# WIFI_BT.net
KiCad netlist of a schematic drawn in Altium Designer
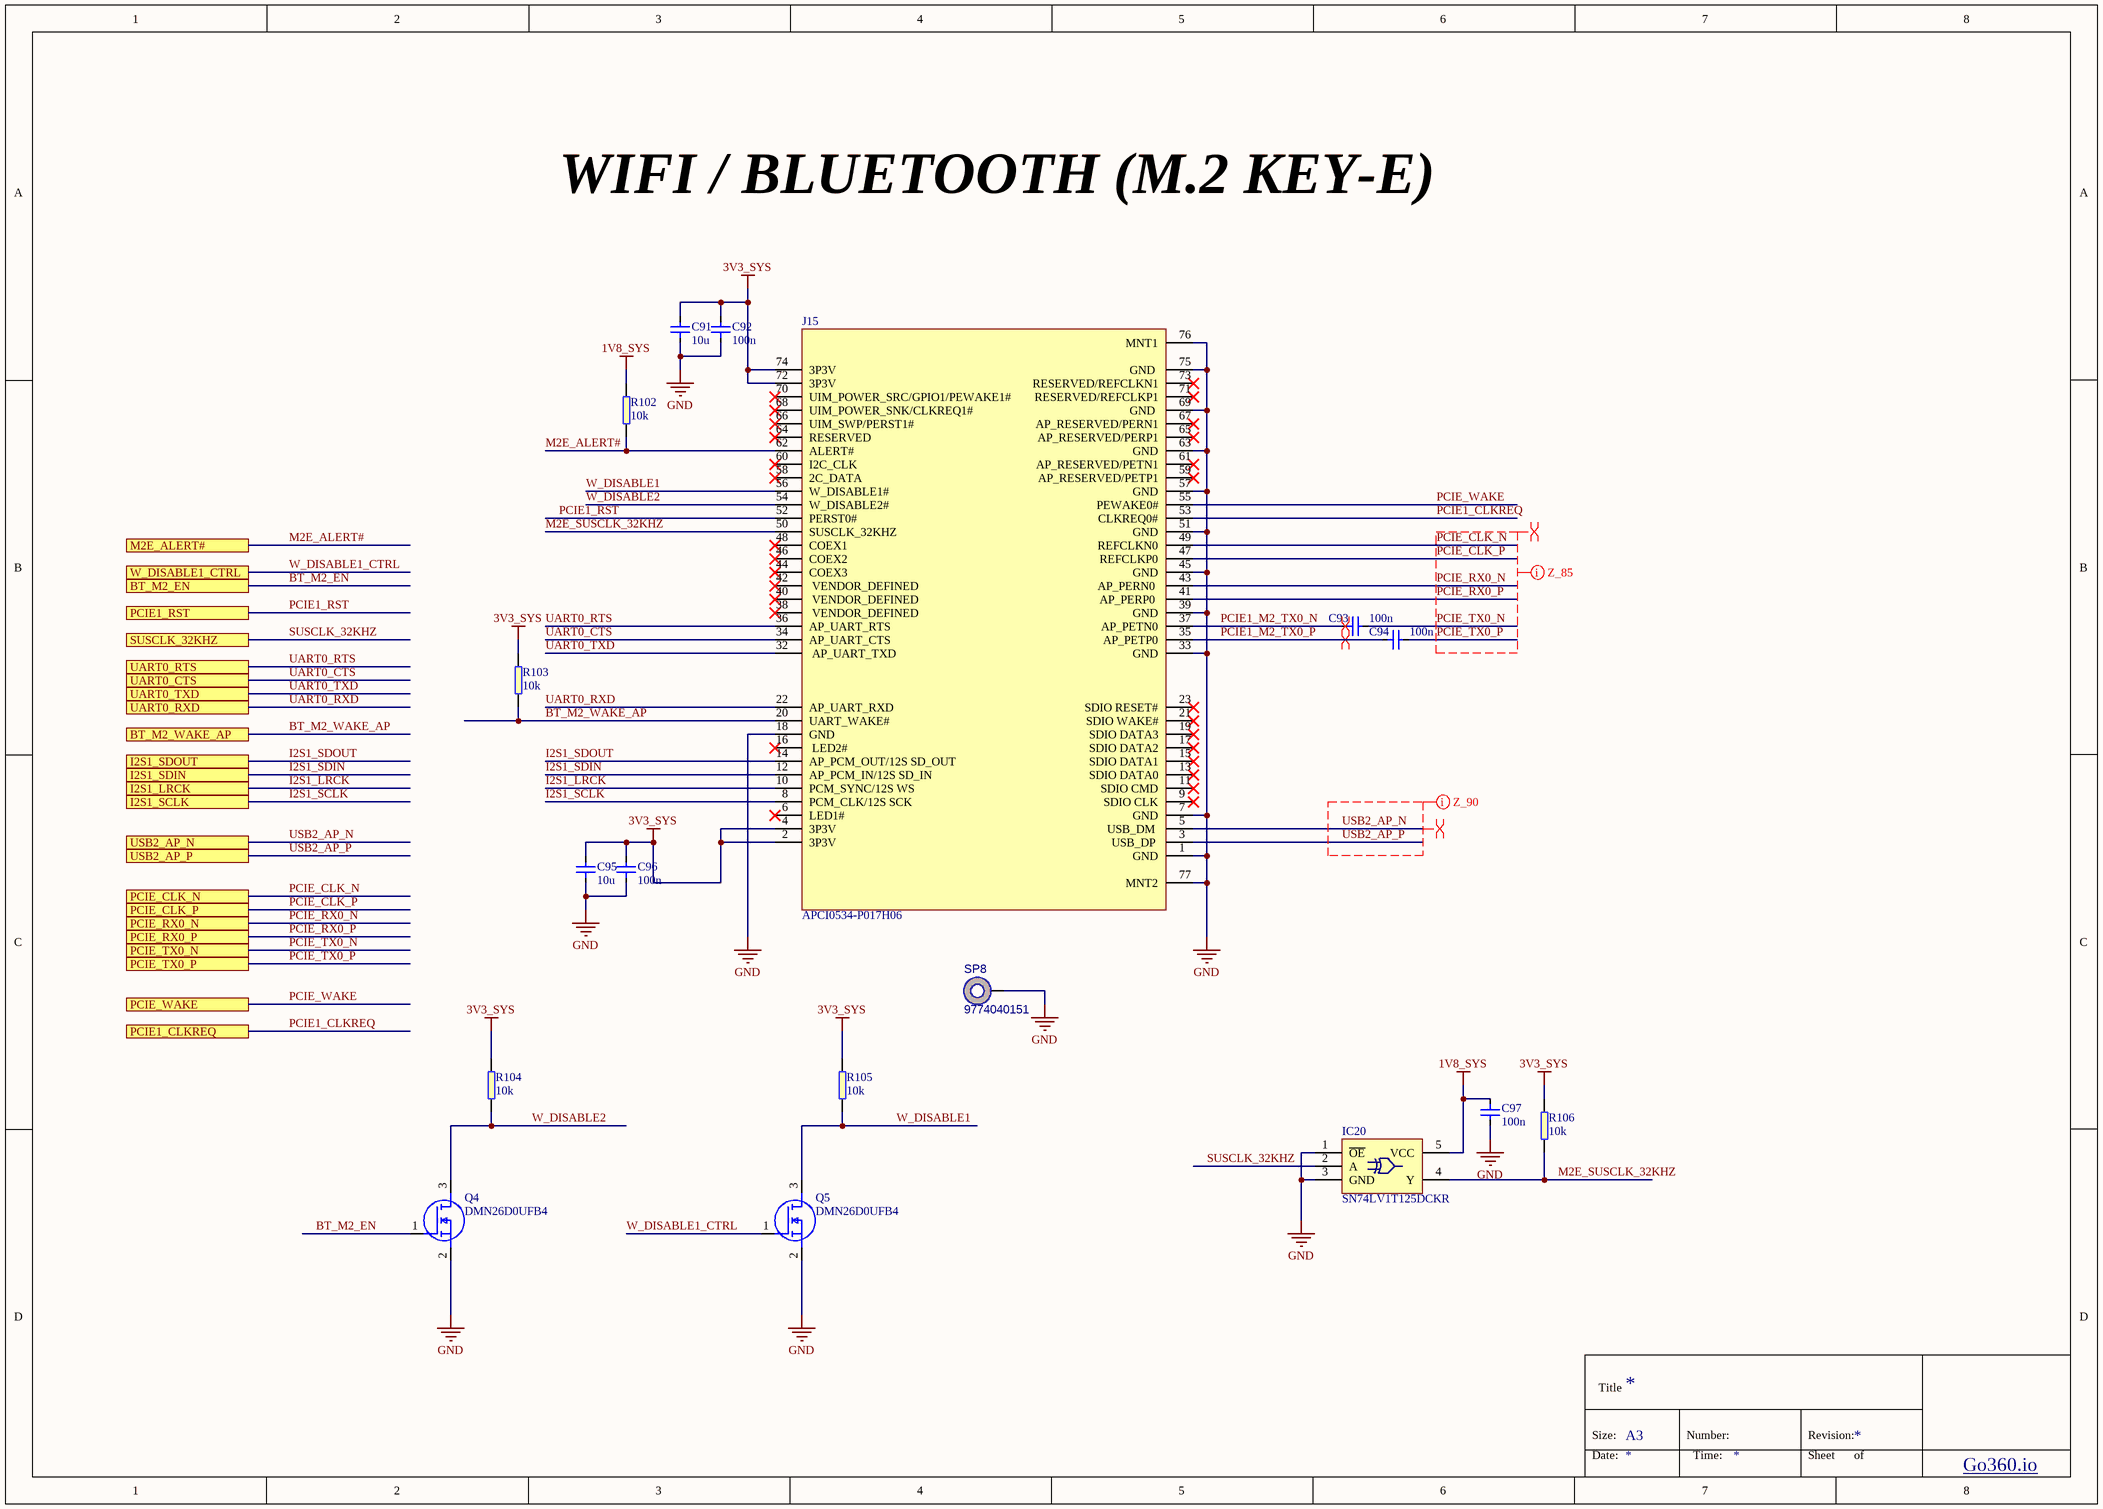
[diagram p0: WIFI_BT.SchDoc]

(export (version "E")
  (design (tool "Eeschema 10.0.6"))
  (components
    (comp (ref "C91")
      (value "10u")
      (footprint "C0603")
      (description "MLCC SMT Capacitor 10uF 0603")
      (fields (field (name "PARTNUMBER") "C_10u_0603") (field (name "MANUFACTURER") "Walsin"))
      (libsource (lib "jetson-nano-baseboard") (part "C_10u_0603"))
    )
    (comp (ref "C92")
      (value "100n")
      (footprint "C0402")
      (description "MLCC SMT Capacitor 100n 0402")
      (fields (field (name "PARTNUMBER") "C_100n_0402") (field (name "MANUFACTURER") "TDK"))
      (libsource (lib "jetson-nano-baseboard") (part "C_100n_0402"))
    )
    (comp (ref "C93")
      (value "100n")
      (footprint "C0402")
      (description "MLCC SMT Capacitor 100n 0402")
      (fields (field (name "PARTNUMBER") "C_100n_0402") (field (name "MANUFACTURER") "TDK"))
      (libsource (lib "jetson-nano-baseboard") (part "C_100n_0402"))
    )
    (comp (ref "C94")
      (value "100n")
      (footprint "C0402")
      (description "MLCC SMT Capacitor 100n 0402")
      (fields (field (name "PARTNUMBER") "C_100n_0402") (field (name "MANUFACTURER") "TDK"))
      (libsource (lib "jetson-nano-baseboard") (part "C_100n_0402"))
    )
    (comp (ref "C95")
      (value "10u")
      (footprint "C0603")
      (description "MLCC SMT Capacitor 10uF 0603")
      (fields (field (name "PARTNUMBER") "C_10u_0603") (field (name "MANUFACTURER") "Walsin"))
      (libsource (lib "jetson-nano-baseboard") (part "C_10u_0603"))
    )
    (comp (ref "C96")
      (value "100n")
      (footprint "C0402")
      (description "MLCC SMT Capacitor 100n 0402")
      (fields (field (name "PARTNUMBER") "C_100n_0402") (field (name "MANUFACTURER") "TDK"))
      (libsource (lib "jetson-nano-baseboard") (part "C_100n_0402"))
    )
    (comp (ref "C97")
      (value "100n")
      (footprint "C0402")
      (description "MLCC SMT Capacitor 100n 0402")
      (fields (field (name "PARTNUMBER") "C_100n_0402") (field (name "MANUFACTURER") "TDK"))
      (libsource (lib "jetson-nano-baseboard") (part "C_100n_0402"))
    )
    (comp (ref "IC20")
      (value "SN74LV1T125DCKR")
      (footprint "SC70-5")
      (description "Buffer, 74LV1T125, 1.6 V to 5.5 V, SOT-23-5")
      (fields (field (name "MANUFACTURER") "Texas Instruments"))
      (libsource (lib "jetson-nano-baseboard") (part "SN74LV1T125"))
    )
    (comp (ref "J15")
      (value "APCI0534-P017H06")
      (footprint "CON_MINIPEX_067_SMT_RA_M2_KEYE_C")
      (libsource (lib "jetson-nano-baseboard") (part "APCI0534-P017H06"))
    )
    (comp (ref "Q4")
      (value "DMN26D0UFB4")
      (footprint "DMN26D0UFB47")
      (description "MOSFET (N-Channel)")
      (fields
        (field (name "MANUFACTURER_PART_NUMBER") "DMN26D0UFB4-7")
        (field (name "MOUSER PART NUMBER") "621-DMN26D0UFB4-7")
      )
      (libsource (lib "jetson-nano-baseboard") (part "DMN26D0UFB4"))
    )
    (comp (ref "Q5")
      (value "DMN26D0UFB4")
      (footprint "DMN26D0UFB47")
      (description "MOSFET (N-Channel)")
      (fields
        (field (name "MANUFACTURER_PART_NUMBER") "DMN26D0UFB4-7")
        (field (name "MOUSER PART NUMBER") "621-DMN26D0UFB4-7")
      )
      (libsource (lib "jetson-nano-baseboard") (part "DMN26D0UFB4"))
    )
    (comp (ref "R102")
      (value "10k")
      (footprint "R0402")
      (description "RES, 10k, 0402")
      (fields (field (name "PARTNUMBER") "R_10k_0402") (field (name "MANUFACTURER") "MULTICOMP"))
      (libsource (lib "jetson-nano-baseboard") (part "R_10k_0402"))
    )
    (comp (ref "R103")
      (value "10k")
      (footprint "R0402")
      (description "RES, 10k, 0402")
      (fields (field (name "PARTNUMBER") "R_10k_0402") (field (name "MANUFACTURER") "MULTICOMP"))
      (libsource (lib "jetson-nano-baseboard") (part "R_10k_0402"))
    )
    (comp (ref "R104")
      (value "10k")
      (footprint "R0402")
      (description "RES, 10k, 0402")
      (fields (field (name "PARTNUMBER") "R_10k_0402") (field (name "MANUFACTURER") "MULTICOMP"))
      (libsource (lib "jetson-nano-baseboard") (part "R_10k_0402"))
    )
    (comp (ref "R105")
      (value "10k")
      (footprint "R0402")
      (description "RES, 10k, 0402")
      (fields (field (name "PARTNUMBER") "R_10k_0402") (field (name "MANUFACTURER") "MULTICOMP"))
      (libsource (lib "jetson-nano-baseboard") (part "R_10k_0402"))
    )
    (comp (ref "R106")
      (value "10k")
      (footprint "R0402")
      (description "RES, 10k, 0402")
      (fields (field (name "PARTNUMBER") "R_10k_0402") (field (name "MANUFACTURER") "MULTICOMP"))
      (libsource (lib "jetson-nano-baseboard") (part "R_10k_0402"))
    )
    (comp (ref "SP8")
      (value "9774040151")
      (footprint "MEC_STANDOFF_PTH_620C380P")
      (description "RND STANDOFF M2.5X0.45 STEEL 4MM")
      (fields (field (name "MANUFACTURER") "WURTH ELEKTRONIK"))
      (libsource (lib "jetson-nano-baseboard") (part "9774040151"))
    )
  )
  (nets
    (net (code "1") (name "/BT_M2_EN") (class "Default")
      (node (ref "Q4") (pin "1") (pinfunction "G_1") (pintype "passive"))
    )
    (net (code "2") (name "/BT_M2_WAKE_AP") (class "Default")
      (node (ref "J15") (pin "20") (pinfunction "UART_WAKE#_20") (pintype "passive"))
      (node (ref "R103") (pin "1") (pintype "passive"))
    )
    (net (code "3") (name "/I2S1_LRCK") (class "Default")
      (node (ref "J15") (pin "10") (pinfunction "PCM_SYNC/12S_WS_10") (pintype "passive"))
    )
    (net (code "4") (name "/I2S1_SCLK") (class "Default")
      (node (ref "J15") (pin "8") (pinfunction "PCM_CLK/12S_SCK_8") (pintype "passive"))
    )
    (net (code "5") (name "/I2S1_SDIN") (class "Default")
      (node (ref "J15") (pin "12") (pinfunction "AP_PCM_IN/12S_SD_IN_12") (pintype "passive"))
    )
    (net (code "6") (name "/I2S1_SDOUT") (class "Default")
      (node (ref "J15") (pin "14") (pinfunction "AP_PCM_OUT/12S_SD_OUT_14") (pintype "passive"))
    )
    (net (code "7") (name "/M2E_ALERT#") (class "Default")
      (node (ref "J15") (pin "62") (pinfunction "ALERT#_62") (pintype "passive"))
      (node (ref "R102") (pin "1") (pintype "passive"))
    )
    (net (code "8") (name "/M2E_SUSCLK_32KHZ") (class "Default")
      (node (ref "IC20") (pin "4") (pinfunction "Y_4") (pintype "passive"))
      (node (ref "J15") (pin "50") (pinfunction "SUSCLK_32KHZ_50") (pintype "passive"))
      (node (ref "R106") (pin "1") (pintype "passive"))
    )
    (net (code "9") (name "/PCIE1_CLKREQ") (class "Default")
      (node (ref "J15") (pin "53") (pinfunction "CLKREQ0#_53") (pintype "passive"))
    )
    (net (code "10") (name "/PCIE1_M2_TX0_N") (class "Default")
      (node (ref "C93") (pin "1") (pinfunction "1_1") (pintype "passive"))
      (node (ref "J15") (pin "37") (pinfunction "AP_PETN0_37") (pintype "passive"))
    )
    (net (code "11") (name "/PCIE1_M2_TX0_P") (class "Default")
      (node (ref "C94") (pin "1") (pinfunction "1_1") (pintype "passive"))
      (node (ref "J15") (pin "35") (pinfunction "AP_PETP0_35") (pintype "passive"))
    )
    (net (code "12") (name "/PCIE1_RST") (class "Default")
      (node (ref "J15") (pin "52") (pinfunction "PERST0#_52") (pintype "passive"))
    )
    (net (code "13") (name "/PCIE_CLK_N") (class "Default")
      (node (ref "J15") (pin "49") (pinfunction "REFCLKN0_49") (pintype "passive"))
    )
    (net (code "14") (name "/PCIE_CLK_P") (class "Default")
      (node (ref "J15") (pin "47") (pinfunction "REFCLKP0_47") (pintype "passive"))
    )
    (net (code "15") (name "/PCIE_RX0_N") (class "Default")
      (node (ref "J15") (pin "43") (pinfunction "AP_PERN0_43") (pintype "passive"))
    )
    (net (code "16") (name "/PCIE_RX0_P") (class "Default")
      (node (ref "J15") (pin "41") (pinfunction "AP_PERP0_41") (pintype "passive"))
    )
    (net (code "17") (name "/PCIE_TX0_N") (class "Default")
      (node (ref "C93") (pin "2") (pinfunction "2_2") (pintype "passive"))
    )
    (net (code "18") (name "/PCIE_TX0_P") (class "Default")
      (node (ref "C94") (pin "2") (pinfunction "2_2") (pintype "passive"))
    )
    (net (code "19") (name "/PCIE_WAKE") (class "Default")
      (node (ref "J15") (pin "55") (pinfunction "PEWAKE0#_55") (pintype "passive"))
    )
    (net (code "20") (name "/SUSCLK_32KHZ") (class "Default")
      (node (ref "IC20") (pin "2") (pinfunction "A_2") (pintype "passive"))
    )
    (net (code "21") (name "/UART0_CTS") (class "Default")
      (node (ref "J15") (pin "34") (pinfunction "AP_UART_CTS_34") (pintype "passive"))
    )
    (net (code "22") (name "/UART0_RTS") (class "Default")
      (node (ref "J15") (pin "36") (pinfunction "AP_UART_RTS_36") (pintype "passive"))
    )
    (net (code "23") (name "/UART0_RXD") (class "Default")
      (node (ref "J15") (pin "22") (pinfunction "AP_UART_RXD_22") (pintype "passive"))
    )
    (net (code "24") (name "/UART0_TXD") (class "Default")
      (node (ref "J15") (pin "32") (pinfunction "_AP_UART_TXD_32") (pintype "passive"))
    )
    (net (code "25") (name "/USB2_AP_N") (class "Default")
      (node (ref "J15") (pin "5") (pinfunction "USB_DM_5") (pintype "passive"))
    )
    (net (code "26") (name "/USB2_AP_P") (class "Default")
      (node (ref "J15") (pin "3") (pinfunction "USB_DP_3") (pintype "passive"))
    )
    (net (code "27") (name "/W_DISABLE1") (class "Default")
      (node (ref "J15") (pin "56") (pinfunction "W_DISABLE1#_56") (pintype "passive"))
      (node (ref "Q5") (pin "3") (pinfunction "D_3") (pintype "passive"))
      (node (ref "R105") (pin "1") (pintype "passive"))
    )
    (net (code "28") (name "/W_DISABLE1_CTRL") (class "Default")
      (node (ref "Q5") (pin "1") (pinfunction "G_1") (pintype "passive"))
    )
    (net (code "29") (name "/W_DISABLE2") (class "Default")
      (node (ref "J15") (pin "54") (pinfunction "W_DISABLE2#_54") (pintype "passive"))
      (node (ref "Q4") (pin "3") (pinfunction "D_3") (pintype "passive"))
      (node (ref "R104") (pin "1") (pintype "passive"))
    )
    (net (code "30") (name "1V8_SYS") (class "Default")
      (node (ref "C97") (pin "1") (pinfunction "1_1") (pintype "passive"))
      (node (ref "IC20") (pin "5") (pinfunction "VCC_5") (pintype "passive"))
      (node (ref "R102") (pin "2") (pintype "passive"))
    )
    (net (code "31") (name "3V3_SYS") (class "Default")
      (node (ref "C91") (pin "2") (pinfunction "2_2") (pintype "passive"))
      (node (ref "C92") (pin "2") (pinfunction "2_2") (pintype "passive"))
      (node (ref "C95") (pin "2") (pinfunction "2_2") (pintype "passive"))
      (node (ref "C96") (pin "2") (pinfunction "2_2") (pintype "passive"))
      (node (ref "J15") (pin "2") (pinfunction "3P3V_2") (pintype "passive"))
      (node (ref "J15") (pin "4") (pinfunction "3P3V_4") (pintype "passive"))
      (node (ref "J15") (pin "72") (pinfunction "3P3V_72") (pintype "passive"))
      (node (ref "J15") (pin "74") (pinfunction "3P3V_74") (pintype "passive"))
      (node (ref "R103") (pin "2") (pintype "passive"))
      (node (ref "R104") (pin "2") (pintype "passive"))
      (node (ref "R105") (pin "2") (pintype "passive"))
      (node (ref "R106") (pin "2") (pintype "passive"))
    )
    (net (code "32") (name "GND") (class "Default")
      (node (ref "C91") (pin "1") (pinfunction "1_1") (pintype "passive"))
      (node (ref "C92") (pin "1") (pinfunction "1_1") (pintype "passive"))
      (node (ref "C95") (pin "1") (pinfunction "1_1") (pintype "passive"))
      (node (ref "C96") (pin "1") (pinfunction "1_1") (pintype "passive"))
      (node (ref "C97") (pin "2") (pinfunction "2_2") (pintype "passive"))
      (node (ref "IC20") (pin "1") (pinfunction "~{OE}_1") (pintype "passive"))
      (node (ref "IC20") (pin "3") (pinfunction "GND_3") (pintype "passive"))
      (node (ref "J15") (pin "1") (pinfunction "GND_1") (pintype "passive"))
      (node (ref "J15") (pin "18") (pinfunction "GND_18") (pintype "passive"))
      (node (ref "J15") (pin "33") (pinfunction "GND_33") (pintype "passive"))
      (node (ref "J15") (pin "39") (pinfunction "GND_39") (pintype "passive"))
      (node (ref "J15") (pin "45") (pinfunction "GND_45") (pintype "passive"))
      (node (ref "J15") (pin "51") (pinfunction "GND_51") (pintype "passive"))
      (node (ref "J15") (pin "57") (pinfunction "GND_57") (pintype "passive"))
      (node (ref "J15") (pin "63") (pinfunction "GND_63") (pintype "passive"))
      (node (ref "J15") (pin "69") (pinfunction "GND_69") (pintype "passive"))
      (node (ref "J15") (pin "7") (pinfunction "GND_7") (pintype "passive"))
      (node (ref "J15") (pin "75") (pinfunction "GND_75") (pintype "passive"))
      (node (ref "J15") (pin "76") (pinfunction "MNT1_76") (pintype "passive"))
      (node (ref "J15") (pin "77") (pinfunction "MNT2_77") (pintype "passive"))
      (node (ref "Q4") (pin "2") (pinfunction "S_2") (pintype "passive"))
      (node (ref "Q5") (pin "2") (pinfunction "S_2") (pintype "passive"))
      (node (ref "SP8") (pin "1") (pinfunction "1_1") (pintype "passive"))
    )
    (net (code "33") (name "unconnected-(J15-2C_DATA-Pad58)") (class "Default")
      (node (ref "J15") (pin "58") (pinfunction "2C_DATA_58") (pintype "passive+no_connect"))
    )
    (net (code "34") (name "unconnected-(J15-AP_RESERVED{slash}PERN1-Pad67)") (class "Default")
      (node (ref "J15") (pin "67") (pinfunction "AP_RESERVED/PERN1_67") (pintype "passive+no_connect"))
    )
    (net (code "35") (name "unconnected-(J15-AP_RESERVED{slash}PERP1-Pad65)") (class "Default")
      (node (ref "J15") (pin "65") (pinfunction "AP_RESERVED/PERP1_65") (pintype "passive+no_connect"))
    )
    (net (code "36") (name "unconnected-(J15-AP_RESERVED{slash}PETN1-Pad61)") (class "Default")
      (node (ref "J15") (pin "61") (pinfunction "AP_RESERVED/PETN1_61") (pintype "passive+no_connect"))
    )
    (net (code "37") (name "unconnected-(J15-AP_RESERVED{slash}PETP1-Pad59)") (class "Default")
      (node (ref "J15") (pin "59") (pinfunction "AP_RESERVED/PETP1_59") (pintype "passive+no_connect"))
    )
    (net (code "38") (name "unconnected-(J15-COEX1-Pad48)") (class "Default")
      (node (ref "J15") (pin "48") (pinfunction "COEX1_48") (pintype "passive+no_connect"))
    )
    (net (code "39") (name "unconnected-(J15-COEX2-Pad46)") (class "Default")
      (node (ref "J15") (pin "46") (pinfunction "COEX2_46") (pintype "passive+no_connect"))
    )
    (net (code "40") (name "unconnected-(J15-COEX3-Pad44)") (class "Default")
      (node (ref "J15") (pin "44") (pinfunction "COEX3_44") (pintype "passive+no_connect"))
    )
    (net (code "41") (name "unconnected-(J15-I2C_CLK-Pad60)") (class "Default")
      (node (ref "J15") (pin "60") (pinfunction "I2C_CLK_60") (pintype "passive+no_connect"))
    )
    (net (code "42") (name "unconnected-(J15-LED1#-Pad6)") (class "Default")
      (node (ref "J15") (pin "6") (pinfunction "LED1#_6") (pintype "passive+no_connect"))
    )
    (net (code "43") (name "unconnected-(J15-RESERVED-Pad64)") (class "Default")
      (node (ref "J15") (pin "64") (pinfunction "RESERVED_64") (pintype "passive+no_connect"))
    )
    (net (code "44") (name "unconnected-(J15-RESERVED{slash}REFCLKN1-Pad73)") (class "Default")
      (node (ref "J15") (pin "73") (pinfunction "RESERVED/REFCLKN1_73") (pintype "passive+no_connect"))
    )
    (net (code "45") (name "unconnected-(J15-RESERVED{slash}REFCLKP1-Pad71)") (class "Default")
      (node (ref "J15") (pin "71") (pinfunction "RESERVED/REFCLKP1_71") (pintype "passive+no_connect"))
    )
    (net (code "46") (name "unconnected-(J15-SDIO_CMD-Pad11)") (class "Default")
      (node (ref "J15") (pin "11") (pinfunction "SDIO_CMD_11") (pintype "passive+no_connect"))
    )
    (net (code "47") (name "unconnected-(J15-SDIO_DATA0-Pad13)") (class "Default")
      (node (ref "J15") (pin "13") (pinfunction "SDIO_DATA0_13") (pintype "passive+no_connect"))
    )
    (net (code "48") (name "unconnected-(J15-SDIO_DATA1-Pad15)") (class "Default")
      (node (ref "J15") (pin "15") (pinfunction "SDIO_DATA1_15") (pintype "passive+no_connect"))
    )
    (net (code "49") (name "unconnected-(J15-SDIO_DATA2-Pad17)") (class "Default")
      (node (ref "J15") (pin "17") (pinfunction "SDIO_DATA2_17") (pintype "passive+no_connect"))
    )
    (net (code "50") (name "unconnected-(J15-SDIO_DATA3-Pad19)") (class "Default")
      (node (ref "J15") (pin "19") (pinfunction "SDIO_DATA3_19") (pintype "passive+no_connect"))
    )
    (net (code "51") (name "unconnected-(J15-SDIO_RESET#-Pad23)") (class "Default")
      (node (ref "J15") (pin "23") (pinfunction "SDIO_RESET#_23") (pintype "passive+no_connect"))
    )
    (net (code "52") (name "unconnected-(J15-SDIO_WAKE#-Pad21)") (class "Default")
      (node (ref "J15") (pin "21") (pinfunction "SDIO_WAKE#_21") (pintype "passive+no_connect"))
    )
    (net (code "53") (name "unconnected-(J15-UIM_POWER_SNK{slash}CLKREQ1#-Pad68)") (class "Default")
      (node (ref "J15") (pin "68") (pinfunction "UIM_POWER_SNK/CLKREQ1#_68") (pintype "passive+no_connect"))
    )
    (net (code "54") (name "unconnected-(J15-UIM_POWER_SRC{slash}GPIO1{slash}PEWAKE1#-Pad70)") (class "Default")
      (node (ref "J15") (pin "70") (pinfunction "UIM_POWER_SRC/GPIO1/PEWAKE1#_70") (pintype "passive+no_connect"))
    )
    (net (code "55") (name "unconnected-(J15-UIM_SWP{slash}PERST1#-Pad66)") (class "Default")
      (node (ref "J15") (pin "66") (pinfunction "UIM_SWP/PERST1#_66") (pintype "passive+no_connect"))
    )
    (net (code "56") (name "unconnected-(J15-_LED2#-Pad16)") (class "Default")
      (node (ref "J15") (pin "16") (pinfunction "_LED2#_16") (pintype "passive+no_connect"))
    )
    (net (code "57") (name "unconnected-(J15-_SDIO_CLK-Pad9)") (class "Default")
      (node (ref "J15") (pin "9") (pinfunction "_SDIO_CLK_9") (pintype "passive+no_connect"))
    )
    (net (code "58") (name "unconnected-(J15-_VENDOR_DEFINED-Pad38)") (class "Default")
      (node (ref "J15") (pin "38") (pinfunction "_VENDOR_DEFINED_38") (pintype "passive+no_connect"))
    )
    (net (code "59") (name "unconnected-(J15-_VENDOR_DEFINED-Pad40)") (class "Default")
      (node (ref "J15") (pin "40") (pinfunction "_VENDOR_DEFINED_40") (pintype "passive+no_connect"))
    )
    (net (code "60") (name "unconnected-(J15-_VENDOR_DEFINED-Pad42)") (class "Default")
      (node (ref "J15") (pin "42") (pinfunction "_VENDOR_DEFINED_42") (pintype "passive+no_connect"))
    )
  )
)
